# VCA.net
KiCad netlist of a schematic drawn in Altium Designer
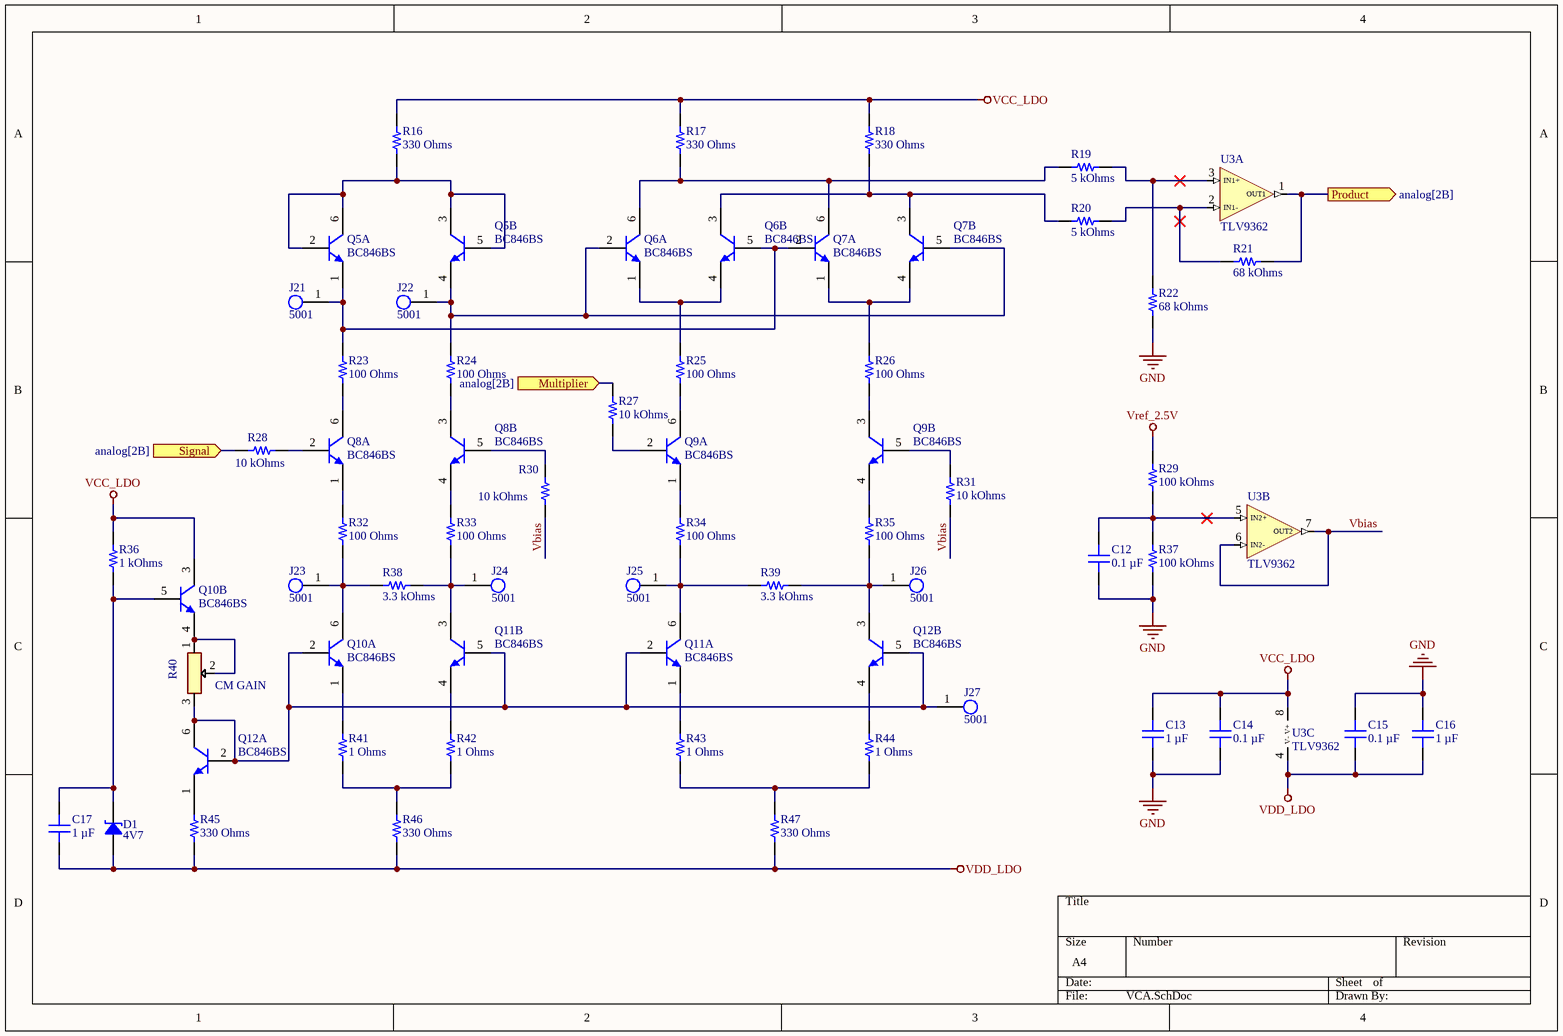
[diagram p0: VCA.SchDoc]

(export (version "E")
  (design (tool "Eeschema 10.0.6"))
  (components
    (comp (ref "C12")
      (value "0.1 µF")
      (footprint "CAP 1206_3216 - 0.8MM")
      (description "CAP CER 0.1UF 50V X7R 1206")
      (fields
        (field (name "PART NUMBER") "885012208087")
        (field (name "CAPACITANCE") "0.1 µF")
        (field (name "MANUFACTURER") "Würth Elektronik")
      )
      (libsource (lib "Celestial Altium Library - altium_library") (part "Capacitor"))
    )
    (comp (ref "C13")
      (value "1 µF")
      (footprint "CAP 1206_3216 - 0.8MM")
      (description "CAP CER 1UF 50V X7R 1206")
      (fields
        (field (name "PART NUMBER") "885012208093")
        (field (name "CAPACITANCE") "1 µF")
        (field (name "MANUFACTURER") "Würth Elektronik")
      )
      (libsource (lib "Celestial Altium Library - altium_library") (part "Capacitor"))
    )
    (comp (ref "C14")
      (value "0.1 µF")
      (footprint "CAP 1206_3216 - 0.8MM")
      (description "CAP CER 0.1UF 50V X7R 1206")
      (fields
        (field (name "PART NUMBER") "885012208087")
        (field (name "CAPACITANCE") "0.1 µF")
        (field (name "MANUFACTURER") "Würth Elektronik")
      )
      (libsource (lib "Celestial Altium Library - altium_library") (part "Capacitor"))
    )
    (comp (ref "C15")
      (value "0.1 µF")
      (footprint "CAP 1206_3216 - 0.8MM")
      (description "CAP CER 0.1UF 50V X7R 1206")
      (fields
        (field (name "PART NUMBER") "885012208087")
        (field (name "CAPACITANCE") "0.1 µF")
        (field (name "MANUFACTURER") "Würth Elektronik")
      )
      (libsource (lib "Celestial Altium Library - altium_library") (part "Capacitor"))
    )
    (comp (ref "C16")
      (value "1 µF")
      (footprint "CAP 1206_3216 - 0.8MM")
      (description "CAP CER 1UF 50V X7R 1206")
      (fields
        (field (name "PART NUMBER") "885012208093")
        (field (name "CAPACITANCE") "1 µF")
        (field (name "MANUFACTURER") "Würth Elektronik")
      )
      (libsource (lib "Celestial Altium Library - altium_library") (part "Capacitor"))
    )
    (comp (ref "C17")
      (value "1 µF")
      (footprint "CAP 1206_3216 - 0.8MM")
      (description "CAP CER 1UF 50V X7R 1206")
      (fields
        (field (name "PART NUMBER") "885012208093")
        (field (name "CAPACITANCE") "1 µF")
        (field (name "MANUFACTURER") "Würth Elektronik")
      )
      (libsource (lib "Celestial Altium Library - altium_library") (part "Capacitor"))
    )
    (comp (ref "D1") (value "4V7") (footprint "SOD323") (libsource (lib "za_koncar") (part "BZX38450-C4V7X")))
    (comp (ref "J21")
      (value "5001")
      (footprint "FP-5001-MFG")
      (description "PC TEST POINT MINIATURE BLACK")
      (libsource (lib "za_koncar") (part "CMP-2000-05181-2"))
    )
    (comp (ref "J22")
      (value "5001")
      (footprint "FP-5001-MFG")
      (description "PC TEST POINT MINIATURE BLACK")
      (libsource (lib "za_koncar") (part "CMP-2000-05181-2"))
    )
    (comp (ref "J23")
      (value "5001")
      (footprint "FP-5001-MFG")
      (description "PC TEST POINT MINIATURE BLACK")
      (libsource (lib "za_koncar") (part "CMP-2000-05181-2"))
    )
    (comp (ref "J24")
      (value "5001")
      (footprint "FP-5001-MFG")
      (description "PC TEST POINT MINIATURE BLACK")
      (libsource (lib "za_koncar") (part "CMP-2000-05181-2"))
    )
    (comp (ref "J25")
      (value "5001")
      (footprint "FP-5001-MFG")
      (description "PC TEST POINT MINIATURE BLACK")
      (libsource (lib "za_koncar") (part "CMP-2000-05181-2"))
    )
    (comp (ref "J26")
      (value "5001")
      (footprint "FP-5001-MFG")
      (description "PC TEST POINT MINIATURE BLACK")
      (libsource (lib "za_koncar") (part "CMP-2000-05181-2"))
    )
    (comp (ref "J27")
      (value "5001")
      (footprint "FP-5001-MFG")
      (description "PC TEST POINT MINIATURE BLACK")
      (libsource (lib "za_koncar") (part "CMP-2000-05181-2"))
    )
    (comp (ref "Q5")
      (value "BC846BS")
      (footprint "TSOP65P210X110-6N")
      (description "65 V, 100 mA matched NPN/NPN general-purpose transistor")
      (libsource (lib "za_koncar") (part "BC846BS"))
    )
    (comp (ref "Q6")
      (value "BC846BS")
      (footprint "TSOP65P210X110-6N")
      (description "65 V, 100 mA matched NPN/NPN general-purpose transistor")
      (libsource (lib "za_koncar") (part "BC846BS"))
    )
    (comp (ref "Q7")
      (value "BC846BS")
      (footprint "TSOP65P210X110-6N")
      (description "65 V, 100 mA matched NPN/NPN general-purpose transistor")
      (libsource (lib "za_koncar") (part "BC846BS"))
    )
    (comp (ref "Q8")
      (value "BC846BS")
      (footprint "TSOP65P210X110-6N")
      (description "65 V, 100 mA matched NPN/NPN general-purpose transistor")
      (libsource (lib "za_koncar") (part "BC846BS"))
    )
    (comp (ref "Q9")
      (value "BC846BS")
      (footprint "TSOP65P210X110-6N")
      (description "65 V, 100 mA matched NPN/NPN general-purpose transistor")
      (libsource (lib "za_koncar") (part "BC846BS"))
    )
    (comp (ref "Q10")
      (value "BC846BS")
      (footprint "TSOP65P210X110-6N")
      (description "65 V, 100 mA matched NPN/NPN general-purpose transistor")
      (libsource (lib "za_koncar") (part "BC846BS"))
    )
    (comp (ref "Q11")
      (value "BC846BS")
      (footprint "TSOP65P210X110-6N")
      (description "65 V, 100 mA matched NPN/NPN general-purpose transistor")
      (libsource (lib "za_koncar") (part "BC846BS"))
    )
    (comp (ref "Q12")
      (value "BC846BS")
      (footprint "TSOP65P210X110-6N")
      (description "65 V, 100 mA matched NPN/NPN general-purpose transistor")
      (libsource (lib "za_koncar") (part "BC846BS"))
    )
    (comp (ref "R16")
      (value "330 Ohms")
      (footprint "YAGEO RES 1206_3216")
      (description "RES SMD 330 OHM 1% 1/4W 1206")
      (fields (field (name "PART NUMBER") "RT1206FRD07330RL") (field (name "MANUFACTURER") "Yageo"))
      (libsource (lib "Celestial Altium Library - altium_library") (part "Resistor"))
    )
    (comp (ref "R17")
      (value "330 Ohms")
      (footprint "YAGEO RES 1206_3216")
      (description "RES SMD 330 OHM 1% 1/4W 1206")
      (fields (field (name "PART NUMBER") "RT1206FRD07330RL") (field (name "MANUFACTURER") "Yageo"))
      (libsource (lib "Celestial Altium Library - altium_library") (part "Resistor"))
    )
    (comp (ref "R18")
      (value "330 Ohms")
      (footprint "YAGEO RES 1206_3216")
      (description "RES SMD 330 OHM 1% 1/4W 1206")
      (fields (field (name "PART NUMBER") "RT1206FRD07330RL") (field (name "MANUFACTURER") "Yageo"))
      (libsource (lib "Celestial Altium Library - altium_library") (part "Resistor"))
    )
    (comp (ref "R19")
      (value "5 kOhms")
      (footprint "YAGEO RES 1206_3216")
      (description "RES 5K OHM 1% 1/4W 1206")
      (fields (field (name "PART NUMBER") "RT1206FRE075KL") (field (name "MANUFACTURER") "Yageo"))
      (libsource (lib "Celestial Altium Library - altium_library") (part "Resistor"))
    )
    (comp (ref "R20")
      (value "5 kOhms")
      (footprint "YAGEO RES 1206_3216")
      (description "RES 5K OHM 1% 1/4W 1206")
      (fields (field (name "PART NUMBER") "RT1206FRE075KL") (field (name "MANUFACTURER") "Yageo"))
      (libsource (lib "Celestial Altium Library - altium_library") (part "Resistor"))
    )
    (comp (ref "R21")
      (value "68 kOhms")
      (footprint "YAGEO RES 1206_3216")
      (description "RES SMD 68K OHM 1% 1/4W 1206")
      (fields (field (name "PART NUMBER") "RT1206FRE0768KL") (field (name "MANUFACTURER") "Yageo"))
      (libsource (lib "Celestial Altium Library - altium_library") (part "Resistor"))
    )
    (comp (ref "R22")
      (value "68 kOhms")
      (footprint "YAGEO RES 1206_3216")
      (description "RES SMD 68K OHM 1% 1/4W 1206")
      (fields (field (name "PART NUMBER") "RT1206FRE0768KL") (field (name "MANUFACTURER") "Yageo"))
      (libsource (lib "Celestial Altium Library - altium_library") (part "Resistor"))
    )
    (comp (ref "R23")
      (value "100 Ohms")
      (footprint "YAGEO RES 1206_3216")
      (description "RES SMD 100 OHM 1% 1/4W 1206")
      (fields (field (name "PART NUMBER") "RT1206FRD07100RL") (field (name "MANUFACTURER") "Yageo"))
      (libsource (lib "Celestial Altium Library - altium_library") (part "Resistor"))
    )
    (comp (ref "R24")
      (value "100 Ohms")
      (footprint "YAGEO RES 1206_3216")
      (description "RES SMD 100 OHM 1% 1/4W 1206")
      (fields (field (name "PART NUMBER") "RT1206FRD07100RL") (field (name "MANUFACTURER") "Yageo"))
      (libsource (lib "Celestial Altium Library - altium_library") (part "Resistor"))
    )
    (comp (ref "R25")
      (value "100 Ohms")
      (footprint "YAGEO RES 1206_3216")
      (description "RES SMD 100 OHM 1% 1/4W 1206")
      (fields (field (name "PART NUMBER") "RT1206FRD07100RL") (field (name "MANUFACTURER") "Yageo"))
      (libsource (lib "Celestial Altium Library - altium_library") (part "Resistor"))
    )
    (comp (ref "R26")
      (value "100 Ohms")
      (footprint "YAGEO RES 1206_3216")
      (description "RES SMD 100 OHM 1% 1/4W 1206")
      (fields (field (name "PART NUMBER") "RT1206FRD07100RL") (field (name "MANUFACTURER") "Yageo"))
      (libsource (lib "Celestial Altium Library - altium_library") (part "Resistor"))
    )
    (comp (ref "R27")
      (value "10 kOhms")
      (footprint "YAGEO RES 1206_3216")
      (description "RES SMD 10K OHM 1% 1/4W 1206")
      (fields (field (name "PART NUMBER") "RT1206FRE0710KL") (field (name "MANUFACTURER") "Yageo"))
      (libsource (lib "Celestial Altium Library - altium_library") (part "Resistor"))
    )
    (comp (ref "R28")
      (value "10 kOhms")
      (footprint "YAGEO RES 1206_3216")
      (description "RES SMD 10K OHM 1% 1/4W 1206")
      (fields (field (name "PART NUMBER") "RT1206FRE0710KL") (field (name "MANUFACTURER") "Yageo"))
      (libsource (lib "Celestial Altium Library - altium_library") (part "Resistor"))
    )
    (comp (ref "R29")
      (value "100 kOhms")
      (footprint "YAGEO RES 1206_3216")
      (description "RES SMD 100K OHM 1% 1/4W 1206")
      (fields (field (name "PART NUMBER") "RT1206FRE07100KL") (field (name "MANUFACTURER") "Yageo"))
      (libsource (lib "Celestial Altium Library - altium_library") (part "Resistor"))
    )
    (comp (ref "R30")
      (value "10 kOhms")
      (footprint "YAGEO RES 1206_3216")
      (description "RES SMD 10K OHM 1% 1/4W 1206")
      (fields (field (name "PART NUMBER") "RT1206FRE0710KL") (field (name "MANUFACTURER") "Yageo"))
      (libsource (lib "Celestial Altium Library - altium_library") (part "Resistor"))
    )
    (comp (ref "R31")
      (value "10 kOhms")
      (footprint "YAGEO RES 1206_3216")
      (description "RES SMD 10K OHM 1% 1/4W 1206")
      (fields (field (name "PART NUMBER") "RT1206FRE0710KL") (field (name "MANUFACTURER") "Yageo"))
      (libsource (lib "Celestial Altium Library - altium_library") (part "Resistor"))
    )
    (comp (ref "R32")
      (value "100 Ohms")
      (footprint "YAGEO RES 1206_3216")
      (description "RES SMD 100 OHM 1% 1/4W 1206")
      (fields (field (name "PART NUMBER") "RT1206FRD07100RL") (field (name "MANUFACTURER") "Yageo"))
      (libsource (lib "Celestial Altium Library - altium_library") (part "Resistor"))
    )
    (comp (ref "R33")
      (value "100 Ohms")
      (footprint "YAGEO RES 1206_3216")
      (description "RES SMD 100 OHM 1% 1/4W 1206")
      (fields (field (name "PART NUMBER") "RT1206FRD07100RL") (field (name "MANUFACTURER") "Yageo"))
      (libsource (lib "Celestial Altium Library - altium_library") (part "Resistor"))
    )
    (comp (ref "R34")
      (value "100 Ohms")
      (footprint "YAGEO RES 1206_3216")
      (description "RES SMD 100 OHM 1% 1/4W 1206")
      (fields (field (name "PART NUMBER") "RT1206FRD07100RL") (field (name "MANUFACTURER") "Yageo"))
      (libsource (lib "Celestial Altium Library - altium_library") (part "Resistor"))
    )
    (comp (ref "R35")
      (value "100 Ohms")
      (footprint "YAGEO RES 1206_3216")
      (description "RES SMD 100 OHM 1% 1/4W 1206")
      (fields (field (name "PART NUMBER") "RT1206FRD07100RL") (field (name "MANUFACTURER") "Yageo"))
      (libsource (lib "Celestial Altium Library - altium_library") (part "Resistor"))
    )
    (comp (ref "R36")
      (value "1 kOhms")
      (footprint "YAGEO RES 1206_3216")
      (description "RES SMD 1K OHM 1% 1/4W 1206")
      (fields (field (name "PART NUMBER") "RT1206FRE071KL") (field (name "MANUFACTURER") "Yageo"))
      (libsource (lib "Celestial Altium Library - altium_library") (part "Resistor"))
    )
    (comp (ref "R37")
      (value "100 kOhms")
      (footprint "YAGEO RES 1206_3216")
      (description "RES SMD 100K OHM 1% 1/4W 1206")
      (fields (field (name "PART NUMBER") "RT1206FRE07100KL") (field (name "MANUFACTURER") "Yageo"))
      (libsource (lib "Celestial Altium Library - altium_library") (part "Resistor"))
    )
    (comp (ref "R38")
      (value "3.3 kOhms")
      (footprint "YAGEO RES 1206_3216")
      (description "RES SMD 3.3K OHM 1% 1/4W 1206")
      (fields (field (name "PART NUMBER") "RT1206FRE073K3L") (field (name "MANUFACTURER") "Yageo"))
      (libsource (lib "Celestial Altium Library - altium_library") (part "Resistor"))
    )
    (comp (ref "R39")
      (value "3.3 kOhms")
      (footprint "YAGEO RES 1206_3216")
      (description "RES SMD 3.3K OHM 1% 1/4W 1206")
      (fields (field (name "PART NUMBER") "RT1206FRE073K3L") (field (name "MANUFACTURER") "Yageo"))
      (libsource (lib "Celestial Altium Library - altium_library") (part "Resistor"))
    )
    (comp (ref "R40")
      (value "TC33X-2-502G")
      (footprint "TC33X2503E")
      (description "Resistor")
      (fields (field (name "MOUSER PART NUMBER") "652-TC33X-2-502G"))
      (libsource (lib "za_koncar") (part "TC33X-2-502G"))
    )
    (comp (ref "R41")
      (value "1 Ohms")
      (footprint "YAGEO RES 1206_3216")
      (description "RES 1 OHM 0.1% 1/4W 1206")
      (fields (field (name "PART NUMBER") "RT1206BRD071RL") (field (name "MANUFACTURER") "Yageo"))
      (libsource (lib "Celestial Altium Library - altium_library") (part "Resistor"))
    )
    (comp (ref "R42")
      (value "1 Ohms")
      (footprint "YAGEO RES 1206_3216")
      (description "RES 1 OHM 0.1% 1/4W 1206")
      (fields (field (name "PART NUMBER") "RT1206BRD071RL") (field (name "MANUFACTURER") "Yageo"))
      (libsource (lib "Celestial Altium Library - altium_library") (part "Resistor"))
    )
    (comp (ref "R43")
      (value "1 Ohms")
      (footprint "YAGEO RES 1206_3216")
      (description "RES 1 OHM 0.1% 1/4W 1206")
      (fields (field (name "PART NUMBER") "RT1206BRD071RL") (field (name "MANUFACTURER") "Yageo"))
      (libsource (lib "Celestial Altium Library - altium_library") (part "Resistor"))
    )
    (comp (ref "R44")
      (value "1 Ohms")
      (footprint "YAGEO RES 1206_3216")
      (description "RES 1 OHM 0.1% 1/4W 1206")
      (fields (field (name "PART NUMBER") "RT1206BRD071RL") (field (name "MANUFACTURER") "Yageo"))
      (libsource (lib "Celestial Altium Library - altium_library") (part "Resistor"))
    )
    (comp (ref "R45")
      (value "330 Ohms")
      (footprint "YAGEO RES 1206_3216")
      (description "RES SMD 330 OHM 1% 1/4W 1206")
      (fields (field (name "PART NUMBER") "RT1206FRD07330RL") (field (name "MANUFACTURER") "Yageo"))
      (libsource (lib "Celestial Altium Library - altium_library") (part "Resistor"))
    )
    (comp (ref "R46")
      (value "330 Ohms")
      (footprint "YAGEO RES 1206_3216")
      (description "RES SMD 330 OHM 1% 1/4W 1206")
      (fields (field (name "PART NUMBER") "RT1206FRD07330RL") (field (name "MANUFACTURER") "Yageo"))
      (libsource (lib "Celestial Altium Library - altium_library") (part "Resistor"))
    )
    (comp (ref "R47")
      (value "330 Ohms")
      (footprint "YAGEO RES 1206_3216")
      (description "RES SMD 330 OHM 1% 1/4W 1206")
      (fields (field (name "PART NUMBER") "RT1206FRD07330RL") (field (name "MANUFACTURER") "Yageo"))
      (libsource (lib "Celestial Altium Library - altium_library") (part "Resistor"))
    )
    (comp (ref "U3")
      (value "TLV9362")
      (footprint "za_koncar:SOIC8-127P600X175-8N")
      (description "TLV936x 10-MHz, 40-V, RRO, Operational Amplifie")
      (libsource (lib "za_koncar") (part "TLV9362"))
    )
  )
  (nets
    (net (code "1") (name "/Multiplier") (class "Default")
      (node (ref "R27") (pin "1") (pinfunction "1_1") (pintype "passive"))
    )
    (net (code "2") (name "/Product") (class "Default")
      (node (ref "R21") (pin "1") (pinfunction "1_1") (pintype "passive"))
      (node (ref "U3") (pin "1") (pinfunction "OUT1_1") (pintype "output"))
    )
    (net (code "3") (name "/Signal") (class "Default")
      (node (ref "R28") (pin "1") (pinfunction "1_1") (pintype "passive"))
    )
    (net (code "4") (name "/Vbias") (class "Default")
      (node (ref "R30") (pin "1") (pinfunction "1_1") (pintype "passive"))
      (node (ref "R31") (pin "1") (pinfunction "1_1") (pintype "passive"))
      (node (ref "U3") (pin "6") (pinfunction "IN2-_6") (pintype "input"))
      (node (ref "U3") (pin "7") (pinfunction "OUT2_7") (pintype "output"))
    )
    (net (code "5") (name "GND") (class "Default")
      (node (ref "C12") (pin "1") (pinfunction "1_1") (pintype "passive"))
      (node (ref "C13") (pin "1") (pinfunction "1_1") (pintype "passive"))
      (node (ref "C14") (pin "1") (pinfunction "1_1") (pintype "passive"))
      (node (ref "C15") (pin "2") (pinfunction "2_2") (pintype "passive"))
      (node (ref "C16") (pin "2") (pinfunction "2_2") (pintype "passive"))
      (node (ref "R22") (pin "2") (pinfunction "2_2") (pintype "passive"))
      (node (ref "R37") (pin "1") (pinfunction "1_1") (pintype "passive"))
    )
    (net (code "6") (name "Net-(Q5A-B1)") (class "Default")
      (node (ref "Q5") (pin "2") (pinfunction "B1_2") (pintype "passive"))
      (node (ref "Q5") (pin "3") (pinfunction "C2_3") (pintype "passive"))
      (node (ref "Q5") (pin "5") (pinfunction "B2_5") (pintype "passive"))
      (node (ref "Q5") (pin "6") (pinfunction "C1_6") (pintype "passive"))
      (node (ref "R16") (pin "1") (pinfunction "1_1") (pintype "passive"))
    )
    (net (code "7") (name "Net-(Q5A-E1)") (class "Default")
      (node (ref "J21") (pin "1") (pinfunction "1_1") (pintype "passive"))
      (node (ref "Q5") (pin "1") (pinfunction "E1_1") (pintype "passive"))
      (node (ref "Q6") (pin "5") (pinfunction "B2_5") (pintype "passive"))
      (node (ref "Q7") (pin "2") (pinfunction "B1_2") (pintype "passive"))
      (node (ref "R23") (pin "2") (pinfunction "2_2") (pintype "passive"))
    )
    (net (code "8") (name "Net-(Q5B-E2)") (class "Default")
      (node (ref "J22") (pin "1") (pinfunction "1_1") (pintype "passive"))
      (node (ref "Q5") (pin "4") (pinfunction "E2_4") (pintype "passive"))
      (node (ref "Q6") (pin "2") (pinfunction "B1_2") (pintype "passive"))
      (node (ref "Q7") (pin "5") (pinfunction "B2_5") (pintype "passive"))
      (node (ref "R24") (pin "2") (pinfunction "2_2") (pintype "passive"))
    )
    (net (code "9") (name "Net-(Q6A-C1)") (class "Default")
      (node (ref "Q6") (pin "6") (pinfunction "C1_6") (pintype "passive"))
      (node (ref "Q7") (pin "6") (pinfunction "C1_6") (pintype "passive"))
      (node (ref "R17") (pin "1") (pinfunction "1_1") (pintype "passive"))
      (node (ref "R19") (pin "2") (pinfunction "2_2") (pintype "passive"))
    )
    (net (code "10") (name "Net-(Q6A-E1)") (class "Default")
      (node (ref "Q6") (pin "1") (pinfunction "E1_1") (pintype "passive"))
      (node (ref "Q6") (pin "4") (pinfunction "E2_4") (pintype "passive"))
      (node (ref "R25") (pin "2") (pinfunction "2_2") (pintype "passive"))
    )
    (net (code "11") (name "Net-(Q6B-C2)") (class "Default")
      (node (ref "Q6") (pin "3") (pinfunction "C2_3") (pintype "passive"))
      (node (ref "Q7") (pin "3") (pinfunction "C2_3") (pintype "passive"))
      (node (ref "R18") (pin "1") (pinfunction "1_1") (pintype "passive"))
      (node (ref "R20") (pin "2") (pinfunction "2_2") (pintype "passive"))
    )
    (net (code "12") (name "Net-(Q7A-E1)") (class "Default")
      (node (ref "Q7") (pin "1") (pinfunction "E1_1") (pintype "passive"))
      (node (ref "Q7") (pin "4") (pinfunction "E2_4") (pintype "passive"))
      (node (ref "R26") (pin "2") (pinfunction "2_2") (pintype "passive"))
    )
    (net (code "13") (name "Net-(Q8A-B1)") (class "Default")
      (node (ref "Q8") (pin "2") (pinfunction "B1_2") (pintype "passive"))
      (node (ref "R28") (pin "2") (pinfunction "2_2") (pintype "passive"))
    )
    (net (code "14") (name "Net-(Q8A-C1)") (class "Default")
      (node (ref "Q8") (pin "6") (pinfunction "C1_6") (pintype "passive"))
      (node (ref "R23") (pin "1") (pinfunction "1_1") (pintype "passive"))
    )
    (net (code "15") (name "Net-(Q8A-E1)") (class "Default")
      (node (ref "Q8") (pin "1") (pinfunction "E1_1") (pintype "passive"))
      (node (ref "R32") (pin "2") (pinfunction "2_2") (pintype "passive"))
    )
    (net (code "16") (name "Net-(Q8B-B2)") (class "Default")
      (node (ref "Q8") (pin "5") (pinfunction "B2_5") (pintype "passive"))
      (node (ref "R30") (pin "2") (pinfunction "2_2") (pintype "passive"))
    )
    (net (code "17") (name "Net-(Q8B-C2)") (class "Default")
      (node (ref "Q8") (pin "3") (pinfunction "C2_3") (pintype "passive"))
      (node (ref "R24") (pin "1") (pinfunction "1_1") (pintype "passive"))
    )
    (net (code "18") (name "Net-(Q8B-E2)") (class "Default")
      (node (ref "Q8") (pin "4") (pinfunction "E2_4") (pintype "passive"))
      (node (ref "R33") (pin "2") (pinfunction "2_2") (pintype "passive"))
    )
    (net (code "19") (name "Net-(Q9A-B1)") (class "Default")
      (node (ref "Q9") (pin "2") (pinfunction "B1_2") (pintype "passive"))
      (node (ref "R27") (pin "2") (pinfunction "2_2") (pintype "passive"))
    )
    (net (code "20") (name "Net-(Q9A-C1)") (class "Default")
      (node (ref "Q9") (pin "6") (pinfunction "C1_6") (pintype "passive"))
      (node (ref "R25") (pin "1") (pinfunction "1_1") (pintype "passive"))
    )
    (net (code "21") (name "Net-(Q9A-E1)") (class "Default")
      (node (ref "Q9") (pin "1") (pinfunction "E1_1") (pintype "passive"))
      (node (ref "R34") (pin "2") (pinfunction "2_2") (pintype "passive"))
    )
    (net (code "22") (name "Net-(Q9B-B2)") (class "Default")
      (node (ref "Q9") (pin "5") (pinfunction "B2_5") (pintype "passive"))
      (node (ref "R31") (pin "2") (pinfunction "2_2") (pintype "passive"))
    )
    (net (code "23") (name "Net-(Q9B-C2)") (class "Default")
      (node (ref "Q9") (pin "3") (pinfunction "C2_3") (pintype "passive"))
      (node (ref "R26") (pin "1") (pinfunction "1_1") (pintype "passive"))
    )
    (net (code "24") (name "Net-(Q9B-E2)") (class "Default")
      (node (ref "Q9") (pin "4") (pinfunction "E2_4") (pintype "passive"))
      (node (ref "R35") (pin "2") (pinfunction "2_2") (pintype "passive"))
    )
    (net (code "25") (name "Net-(Q10A-B1)") (class "Default")
      (node (ref "J27") (pin "1") (pinfunction "1_1") (pintype "passive"))
      (node (ref "Q10") (pin "2") (pinfunction "B1_2") (pintype "passive"))
      (node (ref "Q11") (pin "2") (pinfunction "B1_2") (pintype "passive"))
      (node (ref "Q11") (pin "5") (pinfunction "B2_5") (pintype "passive"))
      (node (ref "Q12") (pin "2") (pinfunction "B1_2") (pintype "passive"))
      (node (ref "Q12") (pin "5") (pinfunction "B2_5") (pintype "passive"))
      (node (ref "Q12") (pin "6") (pinfunction "C1_6") (pintype "passive"))
      (node (ref "R40") (pin "3") (pinfunction "CW_3") (pintype "passive"))
    )
    (net (code "26") (name "Net-(Q10A-C1)") (class "Default")
      (node (ref "J23") (pin "1") (pinfunction "1_1") (pintype "passive"))
      (node (ref "Q10") (pin "6") (pinfunction "C1_6") (pintype "passive"))
      (node (ref "R32") (pin "1") (pinfunction "1_1") (pintype "passive"))
      (node (ref "R38") (pin "2") (pinfunction "2_2") (pintype "passive"))
    )
    (net (code "27") (name "Net-(Q10A-E1)") (class "Default")
      (node (ref "Q10") (pin "1") (pinfunction "E1_1") (pintype "passive"))
      (node (ref "R41") (pin "2") (pinfunction "2_2") (pintype "passive"))
    )
    (net (code "28") (name "Net-(Q10B-B2)") (class "Default")
      (node (ref "C17") (pin "2") (pinfunction "2_2") (pintype "passive"))
      (node (ref "D1") (pin "2") (pinfunction "2_2") (pintype "passive"))
      (node (ref "Q10") (pin "5") (pinfunction "B2_5") (pintype "passive"))
      (node (ref "R36") (pin "1") (pinfunction "1_1") (pintype "passive"))
    )
    (net (code "29") (name "Net-(Q10B-E2)") (class "Default")
      (node (ref "Q10") (pin "4") (pinfunction "E2_4") (pintype "passive"))
      (node (ref "R40") (pin "1") (pinfunction "CCW_1") (pintype "passive"))
      (node (ref "R40") (pin "2") (pinfunction "W_2") (pintype "passive"))
    )
    (net (code "30") (name "Net-(Q11A-C1)") (class "Default")
      (node (ref "J25") (pin "1") (pinfunction "1_1") (pintype "passive"))
      (node (ref "Q11") (pin "6") (pinfunction "C1_6") (pintype "passive"))
      (node (ref "R34") (pin "1") (pinfunction "1_1") (pintype "passive"))
      (node (ref "R39") (pin "2") (pinfunction "2_2") (pintype "passive"))
    )
    (net (code "31") (name "Net-(Q11A-E1)") (class "Default")
      (node (ref "Q11") (pin "1") (pinfunction "E1_1") (pintype "passive"))
      (node (ref "R43") (pin "2") (pinfunction "2_2") (pintype "passive"))
    )
    (net (code "32") (name "Net-(Q11B-C2)") (class "Default")
      (node (ref "J24") (pin "1") (pinfunction "1_1") (pintype "passive"))
      (node (ref "Q11") (pin "3") (pinfunction "C2_3") (pintype "passive"))
      (node (ref "R33") (pin "1") (pinfunction "1_1") (pintype "passive"))
      (node (ref "R38") (pin "1") (pinfunction "1_1") (pintype "passive"))
    )
    (net (code "33") (name "Net-(Q11B-E2)") (class "Default")
      (node (ref "Q11") (pin "4") (pinfunction "E2_4") (pintype "passive"))
      (node (ref "R42") (pin "2") (pinfunction "2_2") (pintype "passive"))
    )
    (net (code "34") (name "Net-(Q12A-E1)") (class "Default")
      (node (ref "Q12") (pin "1") (pinfunction "E1_1") (pintype "passive"))
      (node (ref "R45") (pin "2") (pinfunction "2_2") (pintype "passive"))
    )
    (net (code "35") (name "Net-(Q12B-C2)") (class "Default")
      (node (ref "J26") (pin "1") (pinfunction "1_1") (pintype "passive"))
      (node (ref "Q12") (pin "3") (pinfunction "C2_3") (pintype "passive"))
      (node (ref "R35") (pin "1") (pinfunction "1_1") (pintype "passive"))
      (node (ref "R39") (pin "1") (pinfunction "1_1") (pintype "passive"))
    )
    (net (code "36") (name "Net-(Q12B-E2)") (class "Default")
      (node (ref "Q12") (pin "4") (pinfunction "E2_4") (pintype "passive"))
      (node (ref "R44") (pin "2") (pinfunction "2_2") (pintype "passive"))
    )
    (net (code "37") (name "Net-(R41-Pad1)") (class "Default")
      (node (ref "R41") (pin "1") (pinfunction "1_1") (pintype "passive"))
      (node (ref "R42") (pin "1") (pinfunction "1_1") (pintype "passive"))
      (node (ref "R46") (pin "2") (pinfunction "2_2") (pintype "passive"))
    )
    (net (code "38") (name "Net-(R43-Pad1)") (class "Default")
      (node (ref "R43") (pin "1") (pinfunction "1_1") (pintype "passive"))
      (node (ref "R44") (pin "1") (pinfunction "1_1") (pintype "passive"))
      (node (ref "R47") (pin "2") (pinfunction "2_2") (pintype "passive"))
    )
    (net (code "39") (name "Net-(U3A-IN1+)") (class "Default")
      (node (ref "R19") (pin "1") (pinfunction "1_1") (pintype "passive"))
      (node (ref "R22") (pin "1") (pinfunction "1_1") (pintype "passive"))
      (node (ref "U3") (pin "3") (pinfunction "IN1+_3") (pintype "input"))
    )
    (net (code "40") (name "Net-(U3A-IN1-)") (class "Default")
      (node (ref "R20") (pin "1") (pinfunction "1_1") (pintype "passive"))
      (node (ref "R21") (pin "2") (pinfunction "2_2") (pintype "passive"))
      (node (ref "U3") (pin "2") (pinfunction "IN1-_2") (pintype "input"))
    )
    (net (code "41") (name "Net-(U3B-IN2+)") (class "Default")
      (node (ref "C12") (pin "2") (pinfunction "2_2") (pintype "passive"))
      (node (ref "R29") (pin "1") (pinfunction "1_1") (pintype "passive"))
      (node (ref "R37") (pin "2") (pinfunction "2_2") (pintype "passive"))
      (node (ref "U3") (pin "5") (pinfunction "IN2+_5") (pintype "input"))
    )
    (net (code "42") (name "VCC_LDO") (class "Default")
      (node (ref "C13") (pin "2") (pinfunction "2_2") (pintype "passive"))
      (node (ref "C14") (pin "2") (pinfunction "2_2") (pintype "passive"))
      (node (ref "Q10") (pin "3") (pinfunction "C2_3") (pintype "passive"))
      (node (ref "R16") (pin "2") (pinfunction "2_2") (pintype "passive"))
      (node (ref "R17") (pin "2") (pinfunction "2_2") (pintype "passive"))
      (node (ref "R18") (pin "2") (pinfunction "2_2") (pintype "passive"))
      (node (ref "R36") (pin "2") (pinfunction "2_2") (pintype "passive"))
      (node (ref "U3") (pin "8") (pinfunction "V+_8") (pintype "power_in"))
    )
    (net (code "43") (name "VDD_LDO") (class "Default")
      (node (ref "C15") (pin "1") (pinfunction "1_1") (pintype "passive"))
      (node (ref "C16") (pin "1") (pinfunction "1_1") (pintype "passive"))
      (node (ref "C17") (pin "1") (pinfunction "1_1") (pintype "passive"))
      (node (ref "D1") (pin "1") (pinfunction "1_1") (pintype "passive"))
      (node (ref "R45") (pin "1") (pinfunction "1_1") (pintype "passive"))
      (node (ref "R46") (pin "1") (pinfunction "1_1") (pintype "passive"))
      (node (ref "R47") (pin "1") (pinfunction "1_1") (pintype "passive"))
      (node (ref "U3") (pin "4") (pinfunction "V-_4") (pintype "power_in"))
    )
    (net (code "44") (name "Vref_2.5V") (class "Default")
      (node (ref "R29") (pin "2") (pinfunction "2_2") (pintype "passive"))
    )
  )
)
